# Alimentation.net
KiCad netlist of a schematic drawn in Altium Designer
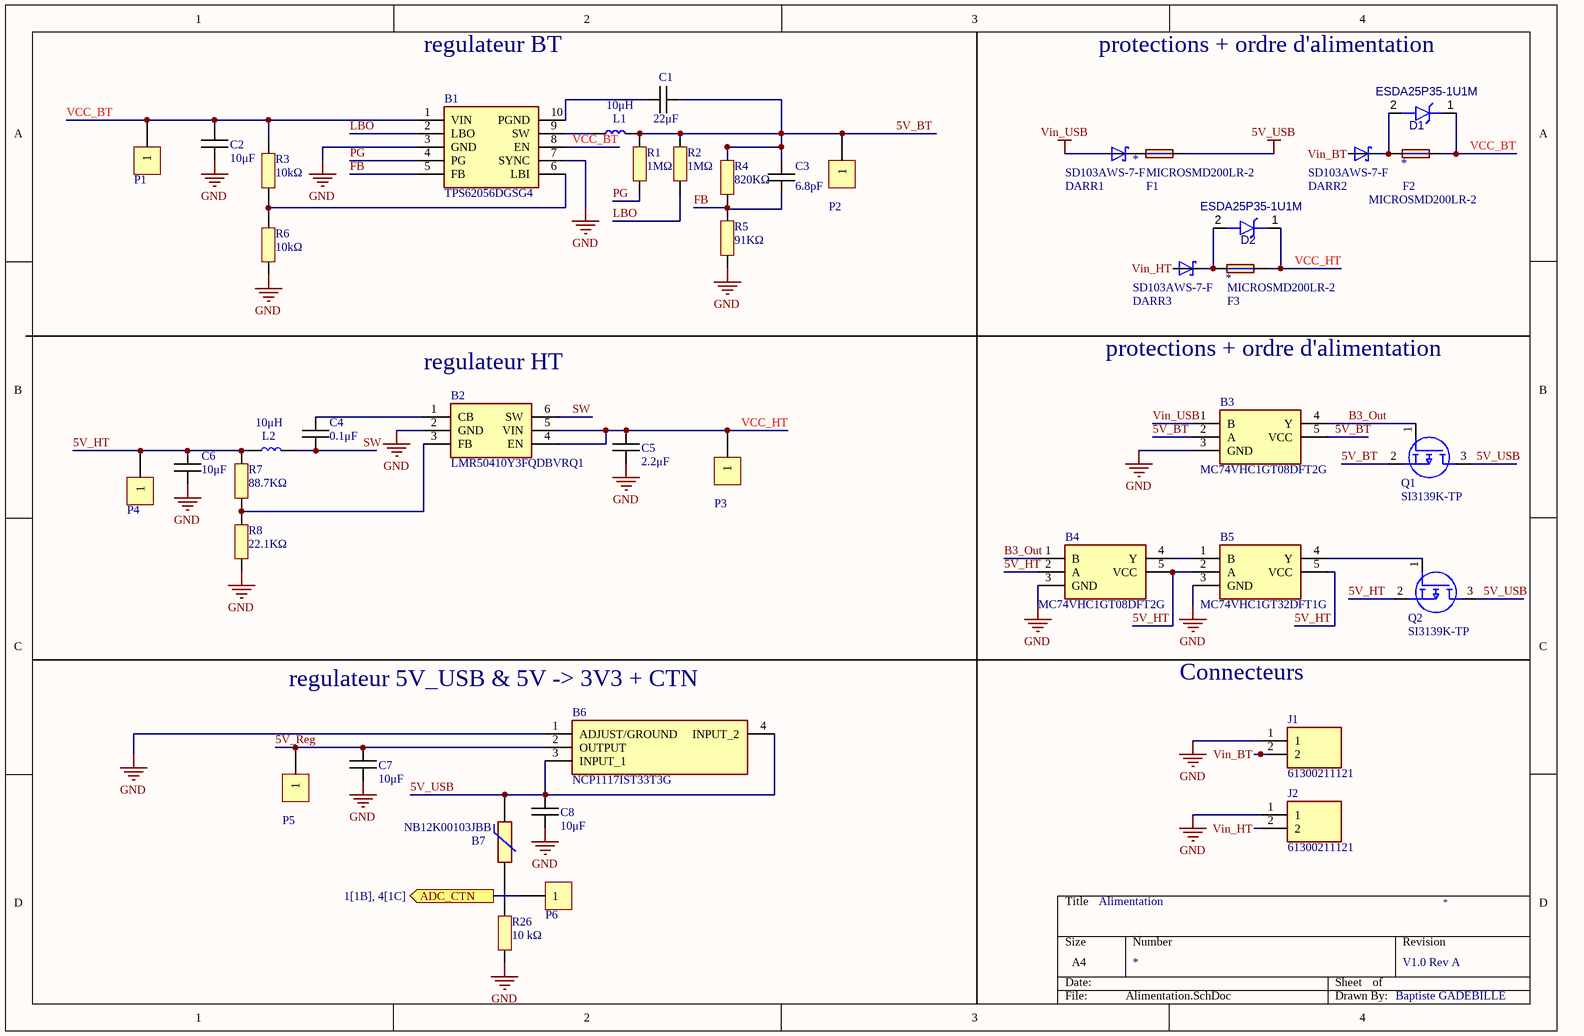
[diagram p0: Alimentation.SchDoc]

(export (version "E")
  (design (tool "Eeschema 10.0.6"))
  (components
    (comp (ref "B1")
      (value "TPS62056DGSG4")
      (footprint "SOP50P490X110-10N")
      (fields (field (name "MOUSER PART NUMBER") "595-TPS62056DGSG4"))
      (libsource (lib "SCHLibrary") (part "TPS62056DGSG4"))
    )
    (comp (ref "B2")
      (value "LMR50410Y3FQDBVRQ1")
      (footprint "SOT95P280X145-6N")
      (fields (field (name "MOUSER PART NUMBER") "595-R50410Y3FQDBVRQ1"))
      (libsource (lib "SCHLibrary") (part "LMR50410Y3FQDBVRQ1"))
    )
    (comp (ref "B3")
      (value "MC74VHC1GT08DFT2G")
      (footprint "SOT65P210X110-5N")
      (description "Single 2-Input AND Gate, TTL Level")
      (libsource (lib "SCHLibrary") (part "MC74VHC1GT08DFT2G"))
    )
    (comp (ref "B4")
      (value "MC74VHC1GT08DFT2G")
      (footprint "SOT65P210X110-5N")
      (description "Single 2-Input AND Gate, TTL Level")
      (libsource (lib "SCHLibrary") (part "MC74VHC1GT08DFT2G"))
    )
    (comp (ref "B5")
      (value "MC74VHC1GT32DFT1G")
      (footprint "SOT65P210X110-5N")
      (description "Single 2-Input OR Gate, TTL Level")
      (fields (field (name "MOUSER PART NUMBER") "863-C74VHC1GT32DFT1G"))
      (libsource (lib "SCHLibrary") (part "MC74VHC1GT32DFT1G"))
    )
    (comp (ref "B6")
      (value "NCP1117IST33T3G")
      (footprint "SOT230P700X180-4N")
      (description "Linear Voltage Regulator IC Positive Fixed 1 Output 1A SOT-223")
      (libsource (lib "SCHLibrary") (part "NCP1117IST33T3G"))
    )
    (comp (ref "B7")
      (value "NB12K00103JBB")
      (footprint "RESC2212X50N")
      (description "NTC SMD Thermistor, NB12K, 10K, 5% AVX 10k 0805 Protection NTC Thermistor, 5s, 2 x 1.25 x 1.3mm")
      (fields (field (name "MOUSER PART NUMBER") "581-NB12K00103JBB"))
      (libsource (lib "SCHLibrary") (part "NB12K00103JBB"))
    )
    (comp (ref "C1")
      (value "22μF")
      (footprint "CAPC1005X06N")
      (libsource (lib "SCHLibrary") (part "Capacitor"))
    )
    (comp (ref "C2")
      (value "10μF")
      (footprint "CAPC1005X06N")
      (libsource (lib "SCHLibrary") (part "Capacitor"))
    )
    (comp (ref "C3")
      (value "6.8pF")
      (footprint "CAPC1005X06N")
      (libsource (lib "SCHLibrary") (part "Capacitor"))
    )
    (comp (ref "C4")
      (value "0.1μF")
      (footprint "CAPC1005X06N")
      (libsource (lib "SCHLibrary") (part "Capacitor"))
    )
    (comp (ref "C5")
      (value "2.2μF")
      (footprint "CAPC1005X06N")
      (libsource (lib "SCHLibrary") (part "Capacitor"))
    )
    (comp (ref "C6")
      (value "10μF")
      (footprint "CAPC1005X06N")
      (libsource (lib "SCHLibrary") (part "Capacitor"))
    )
    (comp (ref "C7")
      (value "10μF")
      (footprint "CAPC1005X06N")
      (libsource (lib "SCHLibrary") (part "Capacitor"))
    )
    (comp (ref "C8")
      (value "10μF")
      (footprint "CAPC1005X06N")
      (libsource (lib "SCHLibrary") (part "Capacitor"))
    )
    (comp (ref "D1")
      (value "ESDA25P35-1U1M")
      (footprint "STM-QFN1610")
      (description "TVS DIODE 22V 41V 1610")
      (libsource (lib "BORDEAUX YNOV CAMPUS") (part "D-TVS-AK-2"))
    )
    (comp (ref "D2")
      (value "ESDA25P35-1U1M")
      (footprint "STM-QFN1610")
      (description "TVS DIODE 22V 41V 1610")
      (libsource (lib "BORDEAUX YNOV CAMPUS") (part "D-TVS-AK-2"))
    )
    (comp (ref "DARR1")
      (value "SD103AWS-7-F")
      (footprint "SD103AWS-7-F")
      (description "Diode Array 3 Independent Schottky 40V 175mA Surface Mount 6-TSSOP, SC-88, SOT-363")
      (libsource (lib "SCHLibrary") (part "SD103AWS-7-F"))
    )
    (comp (ref "DARR2")
      (value "SD103AWS-7-F")
      (footprint "SD103AWS-7-F")
      (description "Diode Array 3 Independent Schottky 40V 175mA Surface Mount 6-TSSOP, SC-88, SOT-363")
      (libsource (lib "SCHLibrary") (part "SD103AWS-7-F"))
    )
    (comp (ref "DARR3")
      (value "SD103AWS-7-F")
      (footprint "SD103AWS-7-F")
      (description "Diode Array 3 Independent Schottky 40V 175mA Surface Mount 6-TSSOP, SC-88, SOT-363")
      (libsource (lib "SCHLibrary") (part "SD103AWS-7-F"))
    )
    (comp (ref "F1")
      (value "MICROSMD200LR-2")
      (footprint "FUSC3225X100N")
      (description "Polymeric PTC Resettable Fuse 6V 2A Ih Surface Mount 1210 _3225 Metric_, Concave")
      (fields (field (name "ALTIUM_VALUE") "*") (field (name "MF") "Littelfuse Inc."))
      (libsource (lib "BORDEAUX YNOV CAMPUS") (part "MICROSMD200LR-2"))
    )
    (comp (ref "F2")
      (value "MICROSMD200LR-2")
      (footprint "FUSC3225X100N")
      (description "Polymeric PTC Resettable Fuse 6V 2A Ih Surface Mount 1210 _3225 Metric_, Concave")
      (fields (field (name "ALTIUM_VALUE") "*") (field (name "MF") "Littelfuse Inc."))
      (libsource (lib "BORDEAUX YNOV CAMPUS") (part "MICROSMD200LR-2"))
    )
    (comp (ref "F3")
      (value "MICROSMD200LR-2")
      (footprint "FUSC3225X100N")
      (description "Polymeric PTC Resettable Fuse 6V 2A Ih Surface Mount 1210 _3225 Metric_, Concave")
      (fields (field (name "ALTIUM_VALUE") "*") (field (name "MF") "Littelfuse Inc."))
      (libsource (lib "BORDEAUX YNOV CAMPUS") (part "MICROSMD200LR-2"))
    )
    (comp (ref "J1")
      (value "61300211121")
      (footprint "61300211121")
      (description "WURTH ELEKTRONIK - 61300211121 - HEADER, 2.54MM, PIN, THT, VERTICAL, 2WAY")
      (libsource (lib "SCHLibrary") (part "61300211121"))
    )
    (comp (ref "J2")
      (value "61300211121")
      (footprint "61300211121")
      (description "WURTH ELEKTRONIK - 61300211121 - HEADER, 2.54MM, PIN, THT, VERTICAL, 2WAY")
      (libsource (lib "SCHLibrary") (part "61300211121"))
    )
    (comp (ref "L1") (value "10μH") (footprint "LQPC1005X06N") (libsource (lib "SCHLibrary") (part "Bobine")))
    (comp (ref "L2") (value "10μH") (footprint "LQPC1005X06N") (libsource (lib "SCHLibrary") (part "Bobine")))
    (comp (ref "P1")
      (value "Plage CMS 10x5")
      (footprint "Plage CMS 10x5")
      (description "Plage de report CMS 10x5mm")
      (libsource (lib "") (part "Plage CMS 10x5_1"))
    )
    (comp (ref "P2")
      (value "Plage CMS 10x5")
      (footprint "Plage CMS 10x5")
      (description "Plage de report CMS 10x5mm")
      (libsource (lib "") (part "Plage CMS 10x5_1"))
    )
    (comp (ref "P3")
      (value "Plage CMS 10x5")
      (footprint "Plage CMS 10x5")
      (description "Plage de report CMS 10x5mm")
      (libsource (lib "") (part "Plage CMS 10x5_1"))
    )
    (comp (ref "P4")
      (value "Plage CMS 10x5")
      (footprint "Plage CMS 10x5")
      (description "Plage de report CMS 10x5mm")
      (libsource (lib "") (part "Plage CMS 10x5_1"))
    )
    (comp (ref "P5")
      (value "Plage CMS 10x5")
      (footprint "Plage CMS 10x5")
      (description "Plage de report CMS 10x5mm")
      (libsource (lib "") (part "Plage CMS 10x5_1"))
    )
    (comp (ref "P6")
      (value "Plage CMS 10x5")
      (footprint "Plage CMS 10x5")
      (description "Plage de report CMS 10x5mm")
      (libsource (lib "SCHLibrary") (part "Plage CMS 10x5"))
    )
    (comp (ref "Q1")
      (value "SI3139K-TP")
      (footprint "SI3139K-TP")
      (description "MOSFET P-Channel MOSFET")
      (libsource (lib "SCHLibrary") (part "SI3139K-TP"))
    )
    (comp (ref "Q2")
      (value "SI3139K-TP")
      (footprint "SI3139K-TP")
      (description "MOSFET P-Channel MOSFET")
      (libsource (lib "SCHLibrary") (part "SI3139K-TP"))
    )
    (comp (ref "R1")
      (value "1MΩ")
      (footprint "RESC1005X06N")
      (libsource (lib "SCHLibrary") (part "Resistor"))
    )
    (comp (ref "R2")
      (value "1MΩ")
      (footprint "RESC1005X06N")
      (libsource (lib "SCHLibrary") (part "Resistor"))
    )
    (comp (ref "R3")
      (value "10kΩ")
      (footprint "RESC1005X06N")
      (libsource (lib "SCHLibrary") (part "Resistor"))
    )
    (comp (ref "R4")
      (value "820KΩ")
      (footprint "RESC1005X06N")
      (libsource (lib "SCHLibrary") (part "Resistor"))
    )
    (comp (ref "R5")
      (value "91KΩ")
      (footprint "RESC1005X06N")
      (libsource (lib "SCHLibrary") (part "Resistor"))
    )
    (comp (ref "R6")
      (value "10kΩ")
      (footprint "RESC1005X06N")
      (libsource (lib "SCHLibrary") (part "Resistor"))
    )
    (comp (ref "R7")
      (value "88.7KΩ")
      (footprint "RESC1005X06N")
      (libsource (lib "SCHLibrary") (part "Resistor"))
    )
    (comp (ref "R8")
      (value "22.1KΩ")
      (footprint "RESC1005X06N")
      (libsource (lib "SCHLibrary") (part "Resistor"))
    )
    (comp (ref "R26")
      (value "10 kΩ")
      (footprint "RESC1005X06N")
      (libsource (lib "SCHLibrary") (part "Resistor"))
    )
  )
  (nets
    (net (code "1") (name "/5V_BT") (class "Default")
      (node (ref "B3") (pin "2") (pinfunction "A_2") (pintype "passive"))
      (node (ref "B3") (pin "5") (pinfunction "VCC_5") (pintype "passive"))
      (node (ref "C1") (pin "2") (pinfunction "2_2") (pintype "passive"))
      (node (ref "C3") (pin "2") (pinfunction "2_2") (pintype "passive"))
      (node (ref "L1") (pin "2") (pinfunction "2_2") (pintype "passive"))
      (node (ref "P2") (pin "1") (pinfunction "1_1") (pintype "passive"))
      (node (ref "Q1") (pin "2") (pinfunction "S_2") (pintype "passive"))
      (node (ref "R1") (pin "1") (pinfunction "1_1") (pintype "passive"))
      (node (ref "R2") (pin "1") (pinfunction "1_1") (pintype "passive"))
      (node (ref "R4") (pin "1") (pinfunction "1_1") (pintype "passive"))
    )
    (net (code "2") (name "/5V_HT") (class "Default")
      (node (ref "B4") (pin "2") (pinfunction "A_2") (pintype "passive"))
      (node (ref "B4") (pin "5") (pinfunction "VCC_5") (pintype "passive"))
      (node (ref "B5") (pin "2") (pinfunction "A_2") (pintype "passive"))
      (node (ref "B5") (pin "5") (pinfunction "VCC_5") (pintype "passive"))
      (node (ref "C6") (pin "1") (pinfunction "1_1") (pintype "passive"))
      (node (ref "L2") (pin "1") (pinfunction "1_1") (pintype "passive"))
      (node (ref "P4") (pin "1") (pinfunction "1_1") (pintype "passive"))
      (node (ref "Q2") (pin "2") (pinfunction "S_2") (pintype "passive"))
      (node (ref "R7") (pin "1") (pinfunction "1_1") (pintype "passive"))
    )
    (net (code "3") (name "/5V_Reg") (class "Default")
      (node (ref "B6") (pin "2") (pinfunction "OUTPUT_2") (pintype "passive"))
      (node (ref "C7") (pin "1") (pinfunction "1_1") (pintype "passive"))
      (node (ref "P5") (pin "1") (pinfunction "1_1") (pintype "passive"))
    )
    (net (code "4") (name "/ADC_CTN") (class "Default")
      (node (ref "P6") (pin "1") (pinfunction "1_1") (pintype "passive"))
    )
    (net (code "5") (name "/B3_Out") (class "Default")
      (node (ref "B3") (pin "4") (pinfunction "Y_4") (pintype "passive"))
      (node (ref "B4") (pin "1") (pinfunction "B_1") (pintype "passive"))
      (node (ref "Q1") (pin "1") (pinfunction "G_1") (pintype "passive"))
    )
    (net (code "6") (name "/FB") (class "Default")
      (node (ref "B1") (pin "5") (pinfunction "FB_5") (pintype "passive"))
      (node (ref "C3") (pin "1") (pinfunction "1_1") (pintype "passive"))
      (node (ref "R4") (pin "2") (pinfunction "2_2") (pintype "passive"))
      (node (ref "R5") (pin "1") (pinfunction "1_1") (pintype "passive"))
    )
    (net (code "7") (name "/LBO") (class "Default")
      (node (ref "B1") (pin "2") (pinfunction "LBO_2") (pintype "passive"))
      (node (ref "R2") (pin "2") (pinfunction "2_2") (pintype "passive"))
    )
    (net (code "8") (name "/PG") (class "Default")
      (node (ref "B1") (pin "4") (pinfunction "PG_4") (pintype "passive"))
      (node (ref "R1") (pin "2") (pinfunction "2_2") (pintype "passive"))
    )
    (net (code "9") (name "/SW") (class "Default")
      (node (ref "B2") (pin "6") (pinfunction "SW_6") (pintype "passive"))
      (node (ref "C4") (pin "2") (pinfunction "2_2") (pintype "passive"))
      (node (ref "L2") (pin "2") (pinfunction "2_2") (pintype "passive"))
    )
    (net (code "10") (name "/VCC_BT") (class "Default")
      (node (ref "B1") (pin "1") (pinfunction "VIN_1") (pintype "passive"))
      (node (ref "B1") (pin "8") (pinfunction "EN_8") (pintype "passive"))
      (node (ref "C2") (pin "1") (pinfunction "1_1") (pintype "passive"))
      (node (ref "D1") (pin "1") (pinfunction "A_1") (pintype "passive"))
      (node (ref "F2") (pin "2") (pinfunction "2_2") (pintype "passive"))
      (node (ref "P1") (pin "1") (pinfunction "1_1") (pintype "passive"))
      (node (ref "R3") (pin "1") (pinfunction "1_1") (pintype "passive"))
    )
    (net (code "11") (name "/VCC_HT") (class "Default")
      (node (ref "B2") (pin "4") (pinfunction "EN_4") (pintype "passive"))
      (node (ref "B2") (pin "5") (pinfunction "VIN_5") (pintype "passive"))
      (node (ref "C5") (pin "1") (pinfunction "1_1") (pintype "passive"))
      (node (ref "D2") (pin "1") (pinfunction "A_1") (pintype "passive"))
      (node (ref "F3") (pin "2") (pinfunction "2_2") (pintype "passive"))
      (node (ref "P3") (pin "1") (pinfunction "1_1") (pintype "passive"))
    )
    (net (code "12") (name "/Vin_BT") (class "Default")
      (node (ref "DARR2") (pin "2") (pinfunction "A_2") (pintype "passive"))
      (node (ref "J1") (pin "2") (pinfunction "2_2") (pintype "passive"))
    )
    (net (code "13") (name "/Vin_HT") (class "Default")
      (node (ref "DARR3") (pin "2") (pinfunction "A_2") (pintype "passive"))
      (node (ref "J2") (pin "2") (pinfunction "2_2") (pintype "passive"))
    )
    (net (code "14") (name "5V_USB") (class "Default")
      (node (ref "B6") (pin "3") (pinfunction "INPUT_1_3") (pintype "passive"))
      (node (ref "B6") (pin "4") (pinfunction "INPUT_2_4") (pintype "passive"))
      (node (ref "B7") (pin "1") (pinfunction "1_1") (pintype "passive"))
      (node (ref "C8") (pin "1") (pinfunction "1_1") (pintype "passive"))
      (node (ref "F1") (pin "2") (pinfunction "2_2") (pintype "passive"))
      (node (ref "Q1") (pin "3") (pinfunction "D_3") (pintype "passive"))
      (node (ref "Q2") (pin "3") (pinfunction "D_3") (pintype "passive"))
    )
    (net (code "15") (name "GND") (class "Default")
      (node (ref "B1") (pin "3") (pinfunction "GND_3") (pintype "passive"))
      (node (ref "B1") (pin "7") (pinfunction "SYNC_7") (pintype "passive"))
      (node (ref "B2") (pin "2") (pinfunction "GND_2") (pintype "passive"))
      (node (ref "B3") (pin "3") (pinfunction "GND_3") (pintype "passive"))
      (node (ref "B4") (pin "3") (pinfunction "GND_3") (pintype "passive"))
      (node (ref "B5") (pin "3") (pinfunction "GND_3") (pintype "passive"))
      (node (ref "B6") (pin "1") (pinfunction "ADJUST/GROUND_1") (pintype "passive"))
      (node (ref "C2") (pin "2") (pinfunction "2_2") (pintype "passive"))
      (node (ref "C5") (pin "2") (pinfunction "2_2") (pintype "passive"))
      (node (ref "C6") (pin "2") (pinfunction "2_2") (pintype "passive"))
      (node (ref "C7") (pin "2") (pinfunction "2_2") (pintype "passive"))
      (node (ref "C8") (pin "2") (pinfunction "2_2") (pintype "passive"))
      (node (ref "J1") (pin "1") (pinfunction "1_1") (pintype "passive"))
      (node (ref "J2") (pin "1") (pinfunction "1_1") (pintype "passive"))
      (node (ref "R26") (pin "2") (pinfunction "2_2") (pintype "passive"))
      (node (ref "R5") (pin "2") (pinfunction "2_2") (pintype "passive"))
      (node (ref "R6") (pin "2") (pinfunction "2_2") (pintype "passive"))
      (node (ref "R8") (pin "2") (pinfunction "2_2") (pintype "passive"))
    )
    (net (code "16") (name "Net-(B1-LBI)") (class "Default")
      (node (ref "B1") (pin "6") (pinfunction "LBI_6") (pintype "passive"))
      (node (ref "R3") (pin "2") (pinfunction "2_2") (pintype "passive"))
      (node (ref "R6") (pin "1") (pinfunction "1_1") (pintype "passive"))
    )
    (net (code "17") (name "Net-(B1-PGND)") (class "Default")
      (node (ref "B1") (pin "10") (pinfunction "PGND_10") (pintype "passive"))
      (node (ref "C1") (pin "1") (pinfunction "1_1") (pintype "passive"))
    )
    (net (code "18") (name "Net-(B1-SW)") (class "Default")
      (node (ref "B1") (pin "9") (pinfunction "SW_9") (pintype "passive"))
      (node (ref "L1") (pin "1") (pinfunction "1_1") (pintype "passive"))
    )
    (net (code "19") (name "Net-(B2-CB)") (class "Default")
      (node (ref "B2") (pin "1") (pinfunction "CB_1") (pintype "passive"))
      (node (ref "C4") (pin "1") (pinfunction "1_1") (pintype "passive"))
    )
    (net (code "20") (name "Net-(B2-FB)") (class "Default")
      (node (ref "B2") (pin "3") (pinfunction "FB_3") (pintype "passive"))
      (node (ref "R7") (pin "2") (pinfunction "2_2") (pintype "passive"))
      (node (ref "R8") (pin "1") (pinfunction "1_1") (pintype "passive"))
    )
    (net (code "21") (name "Net-(B4-Y)") (class "Default")
      (node (ref "B4") (pin "4") (pinfunction "Y_4") (pintype "passive"))
      (node (ref "B5") (pin "1") (pinfunction "B_1") (pintype "passive"))
    )
    (net (code "22") (name "Net-(B5-Y)") (class "Default")
      (node (ref "B5") (pin "4") (pinfunction "Y_4") (pintype "passive"))
      (node (ref "Q2") (pin "1") (pinfunction "G_1") (pintype "passive"))
    )
    (net (code "23") (name "Net-(B7-Pad2)") (class "Default")
      (node (ref "B7") (pin "2") (pinfunction "2_2") (pintype "passive"))
      (node (ref "R26") (pin "1") (pinfunction "1_1") (pintype "passive"))
    )
    (net (code "24") (name "Net-(DARR1-C)") (class "Default")
      (node (ref "DARR1") (pin "1") (pinfunction "C_1") (pintype "passive"))
      (node (ref "F1") (pin "1") (pinfunction "1_1") (pintype "passive"))
    )
    (net (code "25") (name "Net-(DARR2-C)") (class "Default")
      (node (ref "D1") (pin "2") (pinfunction "A_2") (pintype "passive"))
      (node (ref "DARR2") (pin "1") (pinfunction "C_1") (pintype "passive"))
      (node (ref "F2") (pin "1") (pinfunction "1_1") (pintype "passive"))
    )
    (net (code "26") (name "Net-(DARR3-C)") (class "Default")
      (node (ref "D2") (pin "2") (pinfunction "A_2") (pintype "passive"))
      (node (ref "DARR3") (pin "1") (pinfunction "C_1") (pintype "passive"))
      (node (ref "F3") (pin "1") (pinfunction "1_1") (pintype "passive"))
    )
    (net (code "27") (name "Vin_USB") (class "Default")
      (node (ref "B3") (pin "1") (pinfunction "B_1") (pintype "passive"))
      (node (ref "DARR1") (pin "2") (pinfunction "A_2") (pintype "passive"))
    )
  )
)
